# nsq-10.net
KiCad netlist of a schematic drawn in EAGLE
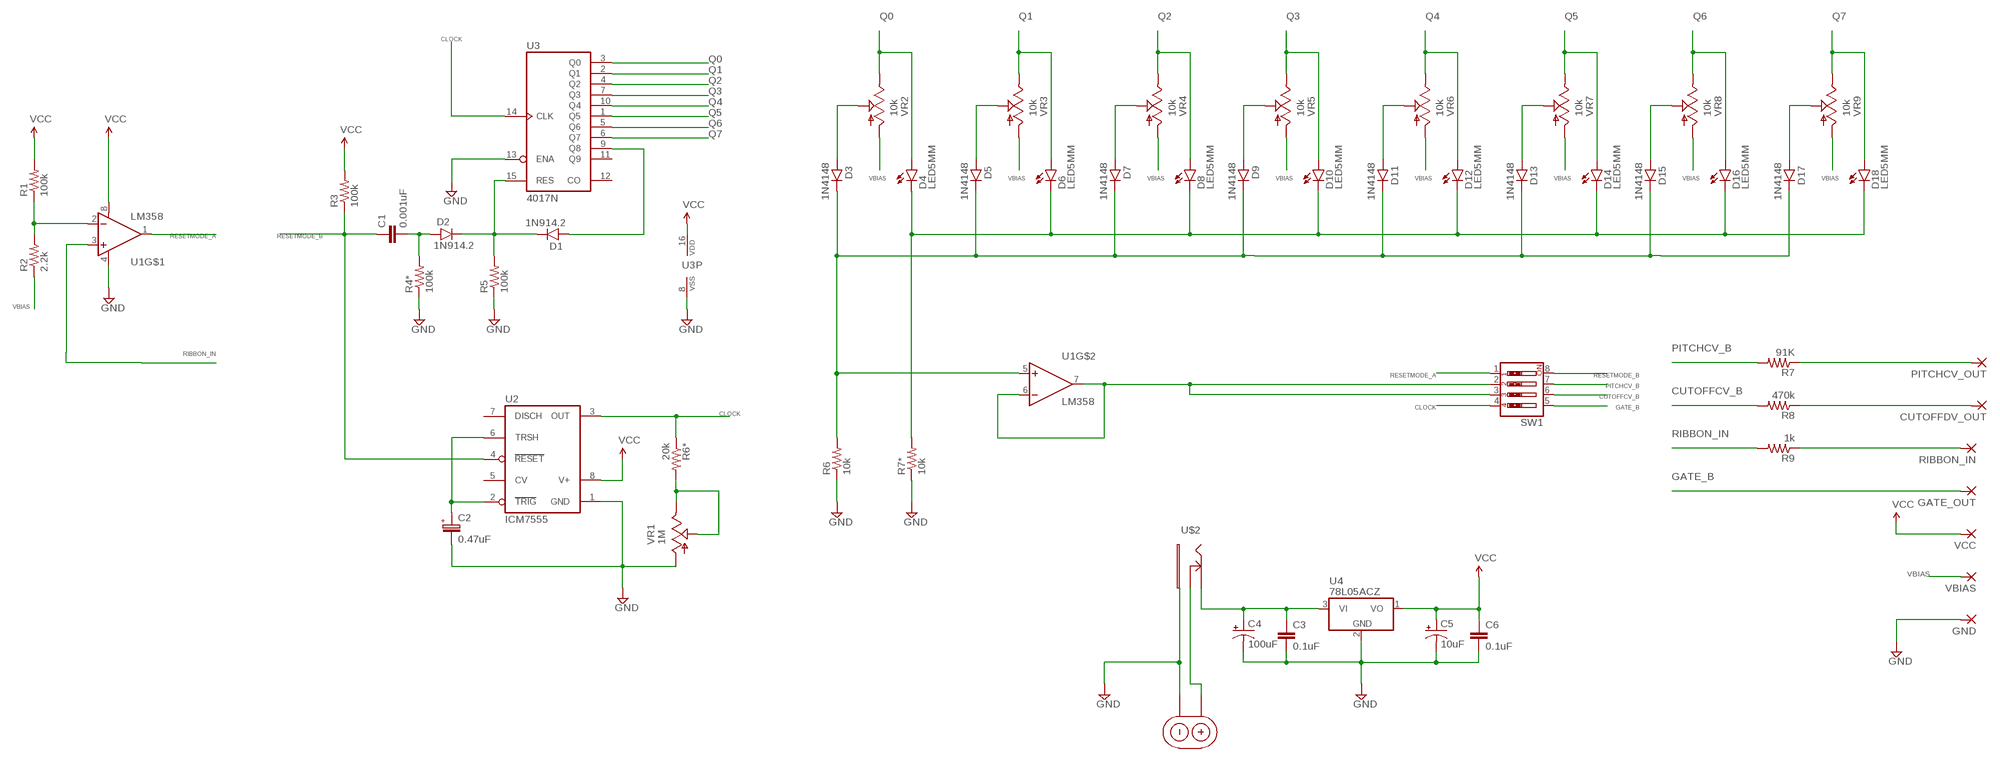
[diagram p0: schematic, sheet 1]

(export (version "E")
  (design (tool "Eeschema 10.0.6"))
  (components
    (comp (ref "C1")
      (value "0.001uF")
      (footprint "eagle-import:CERAMIC_CAP")
      (libsource (lib "eagle-import") (part "CERAMIC_CAPACITOR"))
    )
    (comp (ref "C2")
      (value "0.47uF")
      (footprint "eagle-import:063_025")
      (libsource (lib "eagle-import") (part "063-EU"))
    )
    (comp (ref "C3")
      (value "0.1uF")
      (footprint "eagle-import:CERAMIC_CAP")
      (libsource (lib "eagle-import") (part "CERAMIC_CAPACITOR"))
    )
    (comp (ref "C4")
      (value "100uF")
      (footprint "eagle-import:063_025")
      (libsource (lib "eagle-import") (part "0631"))
    )
    (comp (ref "C5")
      (value "10uF")
      (footprint "eagle-import:063_025")
      (libsource (lib "eagle-import") (part "0631"))
    )
    (comp (ref "C6")
      (value "0.1uF")
      (footprint "eagle-import:CERAMIC_CAP")
      (libsource (lib "eagle-import") (part "CERAMIC_CAPACITOR"))
    )
    (comp (ref "CUTOFFDV_OUT")
      (value "1,6/0,8")
      (footprint "eagle-import:1,6_0,8")
      (libsource (lib "eagle-import") (part "1,6/0,8"))
    )
    (comp (ref "D1")
      (value "1N914.2")
      (footprint "eagle-import:DO35-2")
      (libsource (lib "eagle-import") (part "1N914.2"))
    )
    (comp (ref "D2")
      (value "1N914.2")
      (footprint "eagle-import:DO35-2")
      (libsource (lib "eagle-import") (part "1N914.2"))
    )
    (comp (ref "D3")
      (value "1N4148")
      (footprint "eagle-import:DO35-2")
      (libsource (lib "eagle-import") (part "1N914.2"))
    )
    (comp (ref "D4")
      (value "LED5MM")
      (footprint "eagle-import:LED5MM")
      (libsource (lib "eagle-import") (part "LED5MM"))
    )
    (comp (ref "D5")
      (value "1N4148")
      (footprint "eagle-import:DO35-2")
      (libsource (lib "eagle-import") (part "1N914.2"))
    )
    (comp (ref "D6")
      (value "LED5MM")
      (footprint "eagle-import:LED5MM")
      (libsource (lib "eagle-import") (part "LED5MM"))
    )
    (comp (ref "D7")
      (value "1N4148")
      (footprint "eagle-import:DO35-2")
      (libsource (lib "eagle-import") (part "1N914.2"))
    )
    (comp (ref "D8")
      (value "LED5MM")
      (footprint "eagle-import:LED5MM")
      (libsource (lib "eagle-import") (part "LED5MM"))
    )
    (comp (ref "D9")
      (value "1N4148")
      (footprint "eagle-import:DO35-2")
      (libsource (lib "eagle-import") (part "1N914.2"))
    )
    (comp (ref "D10")
      (value "LED5MM")
      (footprint "eagle-import:LED5MM")
      (libsource (lib "eagle-import") (part "LED5MM"))
    )
    (comp (ref "D11")
      (value "1N4148")
      (footprint "eagle-import:DO35-2")
      (libsource (lib "eagle-import") (part "1N914.2"))
    )
    (comp (ref "D12")
      (value "LED5MM")
      (footprint "eagle-import:LED5MM")
      (libsource (lib "eagle-import") (part "LED5MM"))
    )
    (comp (ref "D13")
      (value "1N4148")
      (footprint "eagle-import:DO35-2")
      (libsource (lib "eagle-import") (part "1N914.2"))
    )
    (comp (ref "D14")
      (value "LED5MM")
      (footprint "eagle-import:LED5MM")
      (libsource (lib "eagle-import") (part "LED5MM"))
    )
    (comp (ref "D15")
      (value "1N4148")
      (footprint "eagle-import:DO35-2")
      (libsource (lib "eagle-import") (part "1N914.2"))
    )
    (comp (ref "D16")
      (value "LED5MM")
      (footprint "eagle-import:LED5MM")
      (libsource (lib "eagle-import") (part "LED5MM"))
    )
    (comp (ref "D17")
      (value "1N4148")
      (footprint "eagle-import:DO35-2")
      (libsource (lib "eagle-import") (part "1N914.2"))
    )
    (comp (ref "D18")
      (value "LED5MM")
      (footprint "eagle-import:LED5MM")
      (libsource (lib "eagle-import") (part "LED5MM"))
    )
    (comp (ref "GATE_OUT")
      (value "1,6/0,8")
      (footprint "eagle-import:1,6_0,8")
      (libsource (lib "eagle-import") (part "1,6/0,8"))
    )
    (comp (ref "GND")
      (value "1,6/0,8")
      (footprint "eagle-import:1,6_0,8")
      (libsource (lib "eagle-import") (part "1,6/0,8"))
    )
    (comp (ref "PITCHCV_OUT")
      (value "1,6/0,8")
      (footprint "eagle-import:1,6_0,8")
      (libsource (lib "eagle-import") (part "1,6/0,8"))
    )
    (comp (ref "R1")
      (value "100k")
      (footprint "eagle-import:RESISTOR")
      (libsource (lib "eagle-import") (part "RESISTOR"))
    )
    (comp (ref "R2")
      (value "2.2k")
      (footprint "eagle-import:RESISTOR")
      (libsource (lib "eagle-import") (part "RESISTOR"))
    )
    (comp (ref "R3")
      (value "100k")
      (footprint "eagle-import:RESISTOR")
      (libsource (lib "eagle-import") (part "RESISTOR"))
    )
    (comp (ref "R4*")
      (value "100k")
      (footprint "eagle-import:RESISTOR")
      (libsource (lib "eagle-import") (part "RESISTOR"))
    )
    (comp (ref "R5")
      (value "100k")
      (footprint "eagle-import:RESISTOR")
      (libsource (lib "eagle-import") (part "RESISTOR"))
    )
    (comp (ref "R6")
      (value "10k")
      (footprint "eagle-import:RESISTOR")
      (libsource (lib "eagle-import") (part "RESISTOR"))
    )
    (comp (ref "R6*")
      (value "20k")
      (footprint "eagle-import:RESISTOR")
      (libsource (lib "eagle-import") (part "RESISTOR"))
    )
    (comp (ref "R7")
      (value "91K")
      (footprint "eagle-import:RESISTOR")
      (libsource (lib "eagle-import") (part "RESISTOR"))
    )
    (comp (ref "R7*")
      (value "10k")
      (footprint "eagle-import:RESISTOR")
      (libsource (lib "eagle-import") (part "RESISTOR"))
    )
    (comp (ref "R8")
      (value "470k")
      (footprint "eagle-import:RESISTOR")
      (libsource (lib "eagle-import") (part "RESISTOR"))
    )
    (comp (ref "R9")
      (value "1k")
      (footprint "eagle-import:RESISTOR")
      (libsource (lib "eagle-import") (part "RESISTOR"))
    )
    (comp (ref "RIBBON_IN")
      (value "1,6/0,8")
      (footprint "eagle-import:1,6_0,8")
      (libsource (lib "eagle-import") (part "1,6/0,8"))
    )
    (comp (ref "SW1")
      (value "SW_DIP-4")
      (footprint "eagle-import:EDG-04")
      (libsource (lib "eagle-import") (part "SW_DIP-4"))
    )
    (comp (ref "U$1")
      (value "9V_BATTERY_CLIP")
      (footprint "eagle-import:9V_BATTERY")
      (libsource (lib "eagle-import") (part "9V_BATTERY_CLIP"))
    )
    (comp (ref "U$2")
      (value "DC_JACK_OFFBOARD")
      (footprint "eagle-import:DC_JACK_OFFBOARD")
      (libsource (lib "eagle-import") (part "DC_JACK_OFFBOARD"))
    )
    (comp (ref "U1")
      (value "LM358")
      (footprint "eagle-import:DIP08")
      (libsource (lib "eagle-import") (part "LM358"))
    )
    (comp (ref "U2")
      (value "ICM7555")
      (footprint "eagle-import:DIL08")
      (fields (field (name "MF") "MAXIM") (field (name "MPN") "ICM7555IPA+"))
      (libsource (lib "eagle-import") (part "ICM7555"))
    )
    (comp (ref "U3")
      (value "4017N")
      (footprint "eagle-import:DIL16")
      (libsource (lib "eagle-import") (part "4017N"))
    )
    (comp (ref "U4")
      (value "78L05ACZ")
      (footprint "eagle-import:TO-92")
      (libsource (lib "eagle-import") (part "78L05ACZ"))
    )
    (comp (ref "VBIAS")
      (value "1,6/0,8")
      (footprint "eagle-import:1,6_0,8")
      (libsource (lib "eagle-import") (part "1,6/0,8"))
    )
    (comp (ref "VCC")
      (value "1,6/0,8")
      (footprint "eagle-import:1,6_0,8")
      (libsource (lib "eagle-import") (part "1,6/0,8"))
    )
    (comp (ref "VR1")
      (value "1M")
      (footprint "eagle-import:B25P")
      (libsource (lib "eagle-import") (part "TRIM_US-B25P"))
    )
    (comp (ref "VR2")
      (value "10k")
      (footprint "eagle-import:B25P")
      (libsource (lib "eagle-import") (part "TRIM_US-B25P"))
    )
    (comp (ref "VR3")
      (value "10k")
      (footprint "eagle-import:B25P")
      (libsource (lib "eagle-import") (part "TRIM_US-B25P"))
    )
    (comp (ref "VR4")
      (value "10k")
      (footprint "eagle-import:B25P")
      (libsource (lib "eagle-import") (part "TRIM_US-B25P"))
    )
    (comp (ref "VR5")
      (value "10k")
      (footprint "eagle-import:B25P")
      (libsource (lib "eagle-import") (part "TRIM_US-B25P"))
    )
    (comp (ref "VR6")
      (value "10k")
      (footprint "eagle-import:B25P")
      (libsource (lib "eagle-import") (part "TRIM_US-B25P"))
    )
    (comp (ref "VR7")
      (value "10k")
      (footprint "eagle-import:B25P")
      (libsource (lib "eagle-import") (part "TRIM_US-B25P"))
    )
    (comp (ref "VR8")
      (value "10k")
      (footprint "eagle-import:B25P")
      (libsource (lib "eagle-import") (part "TRIM_US-B25P"))
    )
    (comp (ref "VR9")
      (value "10k")
      (footprint "eagle-import:B25P")
      (libsource (lib "eagle-import") (part "TRIM_US-B25P"))
    )
  )
  (nets
    (net (code "1") (name "/CLOCK") (class "Default")
      (node (ref "R6*") (pin "1") (pinfunction "1_1") (pintype "passive"))
      (node (ref "SW1") (pin "4") (pinfunction "4_4") (pintype "passive"))
      (node (ref "U2") (pin "3") (pinfunction "OUT_3") (pintype "output"))
      (node (ref "U3") (pin "14") (pinfunction "CLK_14") (pintype "input"))
    )
    (net (code "2") (name "/CUTOFFCV_B") (class "Default")
      (node (ref "R8") (pin "2") (pinfunction "2_2") (pintype "passive"))
      (node (ref "SW1") (pin "6") (pinfunction "6_6") (pintype "passive"))
    )
    (net (code "3") (name "/GATE_B") (class "Default")
      (node (ref "GATE_OUT") (pin "1") (pinfunction "P_1") (pintype "passive"))
      (node (ref "SW1") (pin "5") (pinfunction "5_5") (pintype "passive"))
    )
    (net (code "4") (name "/PITCHCV_B") (class "Default")
      (node (ref "R7") (pin "2") (pinfunction "2_2") (pintype "passive"))
      (node (ref "SW1") (pin "7") (pinfunction "7_7") (pintype "passive"))
    )
    (net (code "5") (name "/Q0") (class "Default")
      (node (ref "D4") (pin "A") (pinfunction "A_A") (pintype "passive"))
      (node (ref "U3") (pin "3") (pinfunction "Q0_3") (pintype "output"))
      (node (ref "VR2") (pin "E") (pinfunction "E_E") (pintype "passive"))
    )
    (net (code "6") (name "/Q1") (class "Default")
      (node (ref "D6") (pin "A") (pinfunction "A_A") (pintype "passive"))
      (node (ref "U3") (pin "2") (pinfunction "Q1_2") (pintype "output"))
      (node (ref "VR3") (pin "E") (pinfunction "E_E") (pintype "passive"))
    )
    (net (code "7") (name "/Q2") (class "Default")
      (node (ref "D8") (pin "A") (pinfunction "A_A") (pintype "passive"))
      (node (ref "U3") (pin "4") (pinfunction "Q2_4") (pintype "output"))
      (node (ref "VR4") (pin "E") (pinfunction "E_E") (pintype "passive"))
    )
    (net (code "8") (name "/Q3") (class "Default")
      (node (ref "D10") (pin "A") (pinfunction "A_A") (pintype "passive"))
      (node (ref "U3") (pin "7") (pinfunction "Q3_7") (pintype "output"))
      (node (ref "VR5") (pin "E") (pinfunction "E_E") (pintype "passive"))
    )
    (net (code "9") (name "/Q4") (class "Default")
      (node (ref "D12") (pin "A") (pinfunction "A_A") (pintype "passive"))
      (node (ref "U3") (pin "10") (pinfunction "Q4_10") (pintype "output"))
      (node (ref "VR6") (pin "E") (pinfunction "E_E") (pintype "passive"))
    )
    (net (code "10") (name "/Q5") (class "Default")
      (node (ref "D14") (pin "A") (pinfunction "A_A") (pintype "passive"))
      (node (ref "U3") (pin "1") (pinfunction "Q5_1") (pintype "output"))
      (node (ref "VR7") (pin "E") (pinfunction "E_E") (pintype "passive"))
    )
    (net (code "11") (name "/Q6") (class "Default")
      (node (ref "D16") (pin "A") (pinfunction "A_A") (pintype "passive"))
      (node (ref "U3") (pin "5") (pinfunction "Q6_5") (pintype "output"))
      (node (ref "VR8") (pin "E") (pinfunction "E_E") (pintype "passive"))
    )
    (net (code "12") (name "/Q7") (class "Default")
      (node (ref "D18") (pin "A") (pinfunction "A_A") (pintype "passive"))
      (node (ref "U3") (pin "6") (pinfunction "Q7_6") (pintype "output"))
      (node (ref "VR9") (pin "E") (pinfunction "E_E") (pintype "passive"))
    )
    (net (code "13") (name "/RESETMODE_A") (class "Default")
      (node (ref "SW1") (pin "1") (pinfunction "1_1") (pintype "passive"))
      (node (ref "U1") (pin "1") (pinfunction "OUT_1") (pintype "output"))
    )
    (net (code "14") (name "/RESETMODE_B") (class "Default")
      (node (ref "C1") (pin "1") (pinfunction "1_1") (pintype "passive"))
      (node (ref "R3") (pin "1") (pinfunction "1_1") (pintype "passive"))
      (node (ref "SW1") (pin "8") (pinfunction "8_8") (pintype "passive"))
      (node (ref "U2") (pin "4") (pinfunction "RESET_4") (pintype "input"))
    )
    (net (code "15") (name "/RIBBON_IN") (class "Default")
      (node (ref "R9") (pin "2") (pinfunction "2_2") (pintype "passive"))
      (node (ref "U1") (pin "3") (pinfunction "+IN_3") (pintype "input"))
    )
    (net (code "16") (name "/VBIAS") (class "Default")
      (node (ref "R2") (pin "1") (pinfunction "1_1") (pintype "passive"))
      (node (ref "VBIAS") (pin "1") (pinfunction "P_1") (pintype "passive"))
      (node (ref "VR2") (pin "A") (pinfunction "A_A") (pintype "passive"))
      (node (ref "VR3") (pin "A") (pinfunction "A_A") (pintype "passive"))
      (node (ref "VR4") (pin "A") (pinfunction "A_A") (pintype "passive"))
      (node (ref "VR5") (pin "A") (pinfunction "A_A") (pintype "passive"))
      (node (ref "VR6") (pin "A") (pinfunction "A_A") (pintype "passive"))
      (node (ref "VR7") (pin "A") (pinfunction "A_A") (pintype "passive"))
      (node (ref "VR8") (pin "A") (pinfunction "A_A") (pintype "passive"))
      (node (ref "VR9") (pin "A") (pinfunction "A_A") (pintype "passive"))
    )
    (net (code "17") (name "GND") (class "Default")
      (node (ref "C2") (pin "-") (pinfunction "-_-") (pintype "passive"))
      (node (ref "C3") (pin "2") (pinfunction "2_2") (pintype "passive"))
      (node (ref "C4") (pin "-") (pinfunction "-_-") (pintype "passive"))
      (node (ref "C5") (pin "-") (pinfunction "-_-") (pintype "passive"))
      (node (ref "C6") (pin "2") (pinfunction "2_2") (pintype "passive"))
      (node (ref "GND") (pin "1") (pinfunction "P_1") (pintype "passive"))
      (node (ref "R4*") (pin "1") (pinfunction "1_1") (pintype "passive"))
      (node (ref "R5") (pin "1") (pinfunction "1_1") (pintype "passive"))
      (node (ref "R6") (pin "1") (pinfunction "1_1") (pintype "passive"))
      (node (ref "R7*") (pin "1") (pinfunction "1_1") (pintype "passive"))
      (node (ref "U$1") (pin "9V_BATTERY_-") (pinfunction "9V_BATTERY_-_9V_BATTERY_-") (pintype "power_in"))
      (node (ref "U$2") (pin "PIN") (pinfunction "PIN_PIN") (pintype "bidirectional"))
      (node (ref "U1") (pin "4") (pinfunction "V-_4") (pintype "power_in"))
      (node (ref "U2") (pin "1") (pinfunction "GND_1") (pintype "power_in"))
      (node (ref "U3") (pin "13") (pinfunction "ENA_13") (pintype "input"))
      (node (ref "U3") (pin "8") (pinfunction "VSS_8") (pintype "power_in"))
      (node (ref "U4") (pin "2") (pinfunction "GND_2") (pintype "passive"))
      (node (ref "VR1") (pin "A") (pinfunction "A_A") (pintype "passive"))
    )
    (net (code "18") (name "Net-(C1-Pad2)") (class "Default")
      (node (ref "C1") (pin "2") (pinfunction "2_2") (pintype "passive"))
      (node (ref "D2") (pin "A") (pinfunction "A_A") (pintype "passive"))
      (node (ref "R4*") (pin "2") (pinfunction "2_2") (pintype "passive"))
    )
    (net (code "19") (name "Net-(CUTOFFDV_OUT-P)") (class "Default")
      (node (ref "CUTOFFDV_OUT") (pin "1") (pinfunction "P_1") (pintype "passive"))
      (node (ref "R8") (pin "1") (pinfunction "1_1") (pintype "passive"))
    )
    (net (code "20") (name "Net-(D3-PadA)") (class "Default")
      (node (ref "D3") (pin "A") (pinfunction "A_A") (pintype "passive"))
      (node (ref "VR2") (pin "S") (pinfunction "S_S") (pintype "passive"))
    )
    (net (code "21") (name "Net-(D5-PadA)") (class "Default")
      (node (ref "D5") (pin "A") (pinfunction "A_A") (pintype "passive"))
      (node (ref "VR3") (pin "S") (pinfunction "S_S") (pintype "passive"))
    )
    (net (code "22") (name "Net-(D7-PadA)") (class "Default")
      (node (ref "D7") (pin "A") (pinfunction "A_A") (pintype "passive"))
      (node (ref "VR4") (pin "S") (pinfunction "S_S") (pintype "passive"))
    )
    (net (code "23") (name "Net-(D9-PadA)") (class "Default")
      (node (ref "D9") (pin "A") (pinfunction "A_A") (pintype "passive"))
      (node (ref "VR5") (pin "S") (pinfunction "S_S") (pintype "passive"))
    )
    (net (code "24") (name "Net-(D10-C)") (class "Default")
      (node (ref "D10") (pin "K") (pinfunction "C_K") (pintype "passive"))
      (node (ref "D12") (pin "K") (pinfunction "C_K") (pintype "passive"))
      (node (ref "D14") (pin "K") (pinfunction "C_K") (pintype "passive"))
      (node (ref "D16") (pin "K") (pinfunction "C_K") (pintype "passive"))
      (node (ref "D18") (pin "K") (pinfunction "C_K") (pintype "passive"))
      (node (ref "D4") (pin "K") (pinfunction "C_K") (pintype "passive"))
      (node (ref "D6") (pin "K") (pinfunction "C_K") (pintype "passive"))
      (node (ref "D8") (pin "K") (pinfunction "C_K") (pintype "passive"))
      (node (ref "R7*") (pin "2") (pinfunction "2_2") (pintype "passive"))
    )
    (net (code "25") (name "Net-(D11-PadA)") (class "Default")
      (node (ref "D11") (pin "A") (pinfunction "A_A") (pintype "passive"))
      (node (ref "VR6") (pin "S") (pinfunction "S_S") (pintype "passive"))
    )
    (net (code "26") (name "Net-(D13-PadA)") (class "Default")
      (node (ref "D13") (pin "A") (pinfunction "A_A") (pintype "passive"))
      (node (ref "VR7") (pin "S") (pinfunction "S_S") (pintype "passive"))
    )
    (net (code "27") (name "Net-(D15-PadA)") (class "Default")
      (node (ref "D15") (pin "A") (pinfunction "A_A") (pintype "passive"))
      (node (ref "VR8") (pin "S") (pinfunction "S_S") (pintype "passive"))
    )
    (net (code "28") (name "Net-(D17-PadA)") (class "Default")
      (node (ref "D17") (pin "A") (pinfunction "A_A") (pintype "passive"))
      (node (ref "VR9") (pin "S") (pinfunction "S_S") (pintype "passive"))
    )
    (net (code "29") (name "Net-(PITCHCV_OUT-P)") (class "Default")
      (node (ref "PITCHCV_OUT") (pin "1") (pinfunction "P_1") (pintype "passive"))
      (node (ref "R7") (pin "1") (pinfunction "1_1") (pintype "passive"))
    )
    (net (code "30") (name "Net-(R6*-Pad2)") (class "Default")
      (node (ref "R6*") (pin "2") (pinfunction "2_2") (pintype "passive"))
      (node (ref "VR1") (pin "E") (pinfunction "E_E") (pintype "passive"))
      (node (ref "VR1") (pin "S") (pinfunction "S_S") (pintype "passive"))
    )
    (net (code "31") (name "Net-(RIBBON_IN-P)") (class "Default")
      (node (ref "R9") (pin "1") (pinfunction "1_1") (pintype "passive"))
      (node (ref "RIBBON_IN") (pin "1") (pinfunction "P_1") (pintype "passive"))
    )
    (net (code "32") (name "Net-(U$1-Pad9V_BATTERY_+)") (class "Default")
      (node (ref "U$1") (pin "9V_BATTERY_+") (pinfunction "9V_BATTERY_+_9V_BATTERY_+") (pintype "power_in"))
      (node (ref "U$2") (pin "CONNECT") (pinfunction "CONNECT_CONNECT") (pintype "bidirectional"))
    )
    (net (code "33") (name "Net-(U1A--IN)") (class "Default")
      (node (ref "R1") (pin "1") (pinfunction "1_1") (pintype "passive"))
      (node (ref "R2") (pin "2") (pinfunction "2_2") (pintype "passive"))
      (node (ref "U1") (pin "2") (pinfunction "-IN_2") (pintype "input"))
    )
    (net (code "34") (name "Net-(U1B-+IN)") (class "Default")
      (node (ref "D11") (pin "C") (pinfunction "C_C") (pintype "passive"))
      (node (ref "D13") (pin "C") (pinfunction "C_C") (pintype "passive"))
      (node (ref "D15") (pin "C") (pinfunction "C_C") (pintype "passive"))
      (node (ref "D17") (pin "C") (pinfunction "C_C") (pintype "passive"))
      (node (ref "D3") (pin "C") (pinfunction "C_C") (pintype "passive"))
      (node (ref "D5") (pin "C") (pinfunction "C_C") (pintype "passive"))
      (node (ref "D7") (pin "C") (pinfunction "C_C") (pintype "passive"))
      (node (ref "D9") (pin "C") (pinfunction "C_C") (pintype "passive"))
      (node (ref "R6") (pin "2") (pinfunction "2_2") (pintype "passive"))
      (node (ref "U1") (pin "5") (pinfunction "+IN_5") (pintype "input"))
    )
    (net (code "35") (name "Net-(U1B--IN)") (class "Default")
      (node (ref "SW1") (pin "2") (pinfunction "2_2") (pintype "passive"))
      (node (ref "SW1") (pin "3") (pinfunction "3_3") (pintype "passive"))
      (node (ref "U1") (pin "6") (pinfunction "-IN_6") (pintype "input"))
      (node (ref "U1") (pin "7") (pinfunction "OUT_7") (pintype "output"))
    )
    (net (code "36") (name "Net-(U2-TRIG)") (class "Default")
      (node (ref "C2") (pin "+") (pinfunction "+_+") (pintype "passive"))
      (node (ref "U2") (pin "2") (pinfunction "TRIG_2") (pintype "bidirectional"))
      (node (ref "U2") (pin "6") (pinfunction "TRSH_6") (pintype "input"))
    )
    (net (code "37") (name "Net-(U3A-Q8)") (class "Default")
      (node (ref "D1") (pin "A") (pinfunction "A_A") (pintype "passive"))
      (node (ref "U3") (pin "9") (pinfunction "Q8_9") (pintype "output"))
    )
    (net (code "38") (name "Net-(U3A-RES)") (class "Default")
      (node (ref "D1") (pin "C") (pinfunction "C_C") (pintype "passive"))
      (node (ref "D2") (pin "C") (pinfunction "C_C") (pintype "passive"))
      (node (ref "R5") (pin "2") (pinfunction "2_2") (pintype "passive"))
      (node (ref "U3") (pin "15") (pinfunction "RES_15") (pintype "input"))
    )
    (net (code "39") (name "Net-(U4-VI)") (class "Default")
      (node (ref "C3") (pin "1") (pinfunction "1_1") (pintype "passive"))
      (node (ref "C4") (pin "+") (pinfunction "+_+") (pintype "passive"))
      (node (ref "U$2") (pin "SLEEVE") (pinfunction "SLEEVE_SLEEVE") (pintype "bidirectional"))
      (node (ref "U4") (pin "3") (pinfunction "VI_3") (pintype "input"))
    )
    (net (code "40") (name "VCC") (class "Default")
      (node (ref "C5") (pin "+") (pinfunction "+_+") (pintype "passive"))
      (node (ref "C6") (pin "1") (pinfunction "1_1") (pintype "passive"))
      (node (ref "R1") (pin "2") (pinfunction "2_2") (pintype "passive"))
      (node (ref "R3") (pin "2") (pinfunction "2_2") (pintype "passive"))
      (node (ref "U1") (pin "8") (pinfunction "V+_8") (pintype "power_in"))
      (node (ref "U2") (pin "8") (pinfunction "V+_8") (pintype "power_in"))
      (node (ref "U3") (pin "16") (pinfunction "VDD_16") (pintype "power_in"))
      (node (ref "U4") (pin "1") (pinfunction "VO_1") (pintype "passive"))
      (node (ref "VCC") (pin "1") (pinfunction "P_1") (pintype "passive"))
    )
    (net (code "41") (name "unconnected-(U2-CV-Pad5)") (class "Default")
      (node (ref "U2") (pin "5") (pinfunction "CV_5") (pintype "passive"))
    )
    (net (code "42") (name "unconnected-(U2-DISCH-Pad7)") (class "Default")
      (node (ref "U2") (pin "7") (pinfunction "DISCH_7") (pintype "input"))
    )
    (net (code "43") (name "unconnected-(U3A-CO-Pad12)") (class "Default")
      (node (ref "U3") (pin "12") (pinfunction "CO_12") (pintype "output"))
    )
    (net (code "44") (name "unconnected-(U3A-Q9-Pad11)") (class "Default")
      (node (ref "U3") (pin "11") (pinfunction "Q9_11") (pintype "output"))
    )
  )
)
